# SkyKontrol-smartDisplay.net
KiCad netlist of a schematic drawn in EAGLE
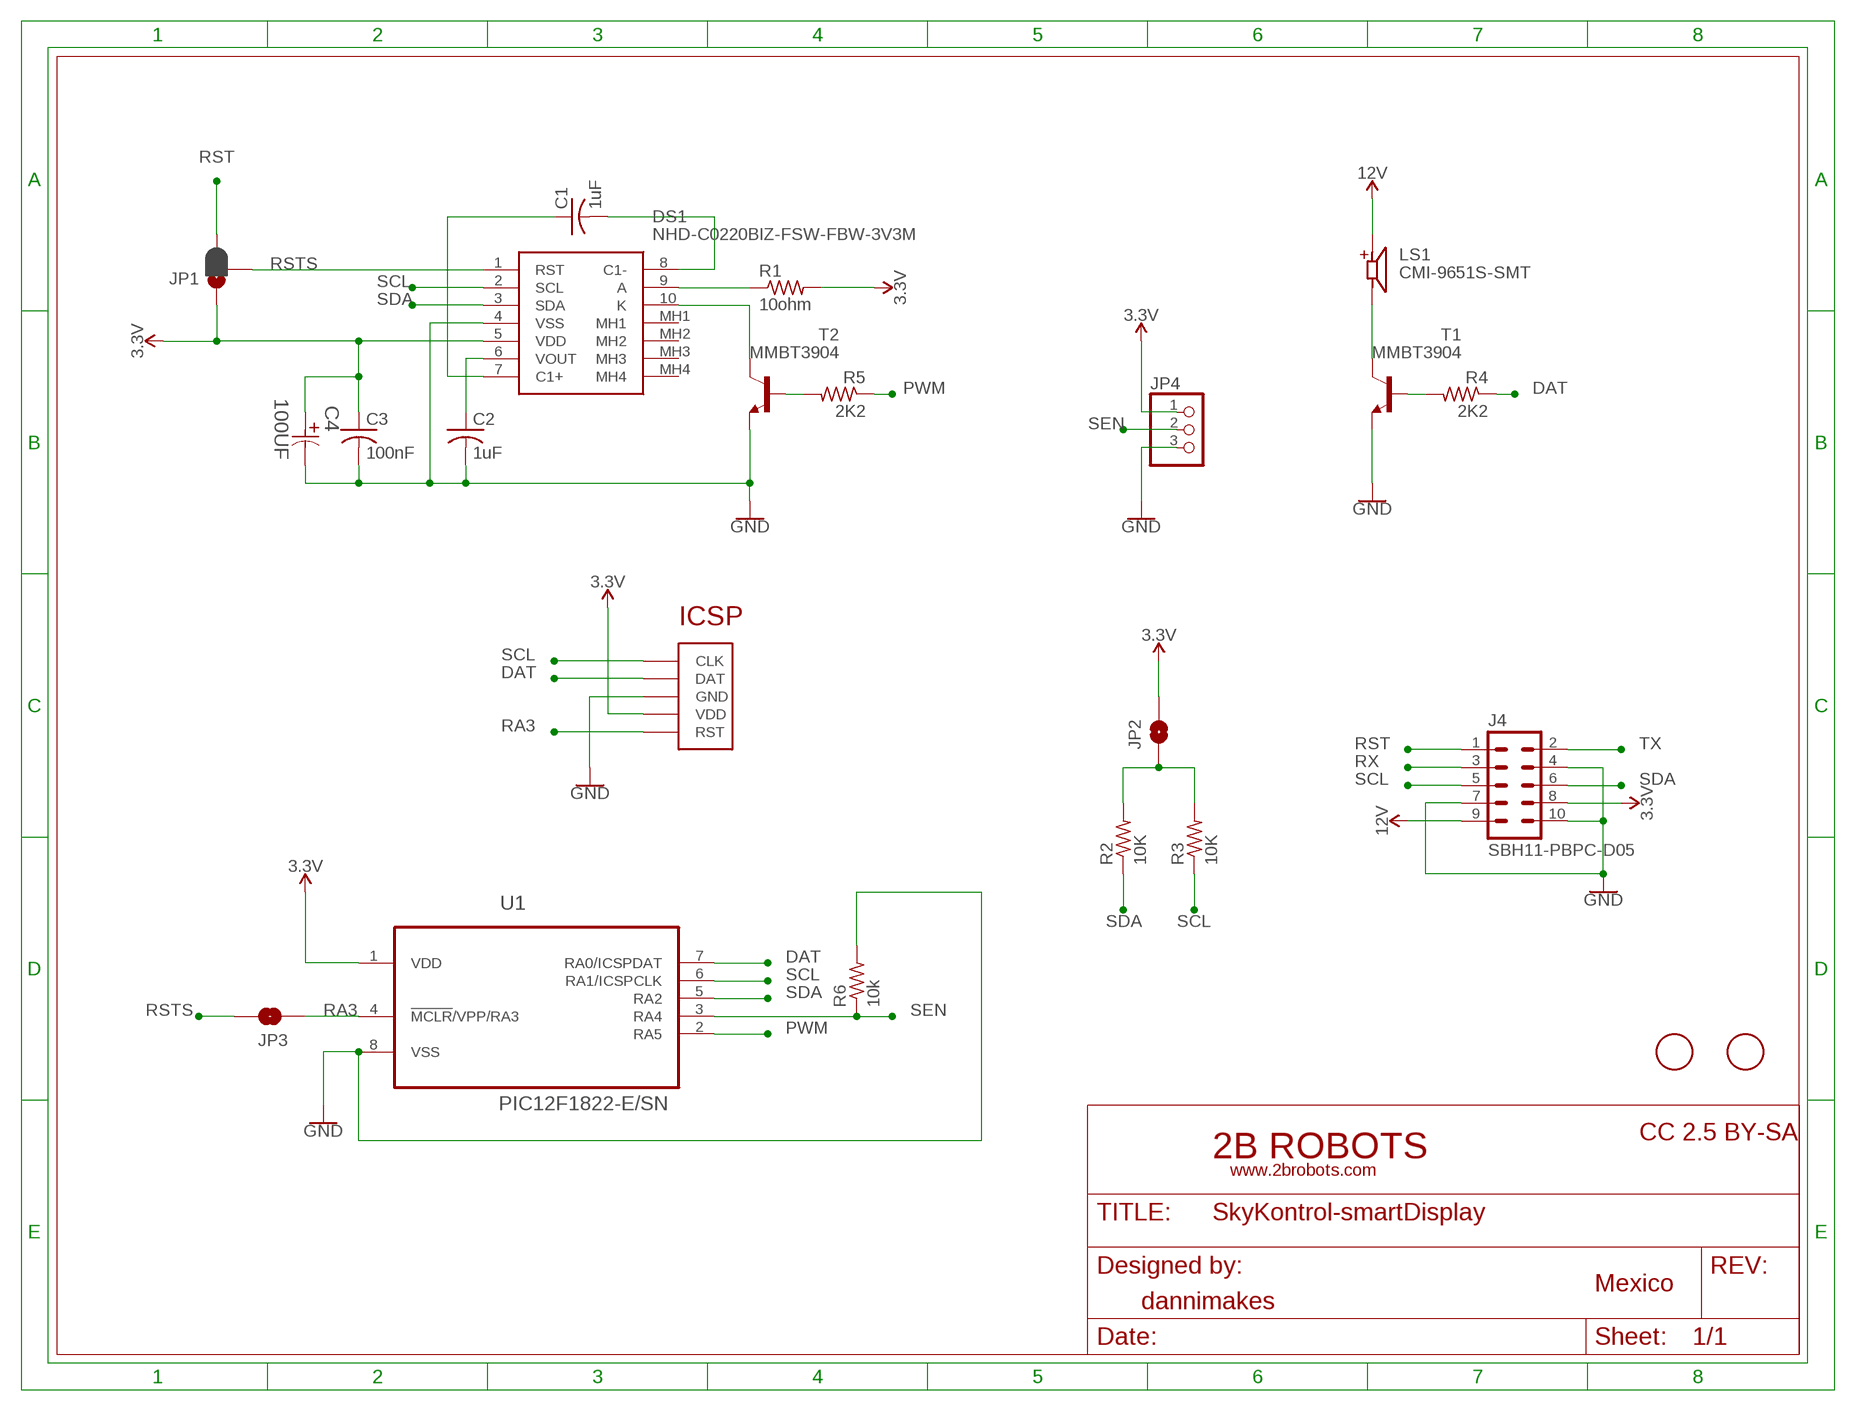
[diagram p0: schematic, sheet 1]

(export (version "E")
  (design (tool "Eeschema 10.0.6"))
  (components
    (comp (ref "C1")
      (value "1uF")
      (footprint "eagle-import:C0603K")
      (libsource (lib "eagle-import") (part "C-USC0603K"))
    )
    (comp (ref "C2")
      (value "1uF")
      (footprint "eagle-import:C0603K")
      (libsource (lib "eagle-import") (part "C-USC0603K"))
    )
    (comp (ref "C3")
      (value "100nF")
      (footprint "eagle-import:C0603K")
      (libsource (lib "eagle-import") (part "C-USC0603K"))
    )
    (comp (ref "C4")
      (value "100UF")
      (footprint "eagle-import:CAPAE660X800N")
      (fields (field (name "MPN") "EEE-HA1E101XP") (field (name "TOLERANCE") "±20 %"))
      (libsource (lib "eagle-import") (part "EEE--CASE-D8HA1E101XP"))
    )
    (comp (ref "DS1")
      (value "NHD-C0220BIZ-FSW-FBW-3V3M")
      (footprint "eagle-import:NHDC0220BIZFSWFBW3V3M")
      (fields (field (name "MOUSER_PART_NUMBER") "763-C0220BIZ-FSW-FBW"))
      (libsource (lib "eagle-import") (part "NHD-C0220BIZ-FSW-FBW-3V3M"))
    )
    (comp (ref "J4")
      (value "SBH11-PBPC-D05")
      (footprint "eagle-import:SBH11-PBPC-D05")
      (libsource (lib "eagle-import") (part "SBH11-PBPC-D05"))
    )
    (comp (ref "JP1")
      (value "JUMPER-SMT_3_1-NC_PASTE_SILK")
      (footprint "eagle-import:SMT-JUMPER_3_1-NC_PASTE_SILK")
      (libsource (lib "eagle-import") (part "JUMPER-SMT_3_1-NC_PASTE_SILK"))
    )
    (comp (ref "JP2")
      (value "JUMPER-SMT_2_NO_SILK")
      (footprint "eagle-import:SMT-JUMPER_2_NO_SILK")
      (libsource (lib "eagle-import") (part "JUMPER-SMT_2_NO_SILK"))
    )
    (comp (ref "JP3")
      (value "JUMPER-SMT_2_NO_SILK")
      (footprint "eagle-import:SMT-JUMPER_2_NO_SILK")
      (libsource (lib "eagle-import") (part "JUMPER-SMT_2_NO_SILK"))
    )
    (comp (ref "JP4")
      (value "PINHD-1X3CB")
      (footprint "eagle-import:1X03-CLEANBIG")
      (libsource (lib "eagle-import") (part "PINHD-1X3CB"))
    )
    (comp (ref "LS1")
      (value "CMI-9651S-SMT")
      (footprint "eagle-import:CUI_CMI-9651S-SMT")
      (fields (field (name "MANUFACTURER") "CUI INC"))
      (libsource (lib "eagle-import") (part "CMI-9651S-SMT"))
    )
    (comp (ref "R1")
      (value "10ohm")
      (footprint "eagle-import:R0805")
      (libsource (lib "eagle-import") (part "R-US_R0805"))
    )
    (comp (ref "R2")
      (value "10K")
      (footprint "eagle-import:R0805")
      (libsource (lib "eagle-import") (part "R-US_R0805"))
    )
    (comp (ref "R3")
      (value "10K")
      (footprint "eagle-import:R0805")
      (libsource (lib "eagle-import") (part "R-US_R0805"))
    )
    (comp (ref "R4")
      (value "2K2")
      (footprint "eagle-import:R0805")
      (libsource (lib "eagle-import") (part "R-US_R0805"))
    )
    (comp (ref "R5")
      (value "2K2")
      (footprint "eagle-import:R0805")
      (libsource (lib "eagle-import") (part "R-US_R0805"))
    )
    (comp (ref "R6")
      (value "10k")
      (footprint "eagle-import:R0805")
      (libsource (lib "eagle-import") (part "R-US_R0805"))
    )
    (comp (ref "T1")
      (value "MMBT3904")
      (footprint "eagle-import:SOT23-BEC")
      (libsource (lib "eagle-import") (part "-NPN-SOT23-BECMMBT3904LT1"))
    )
    (comp (ref "T2")
      (value "MMBT3904")
      (footprint "eagle-import:SOT23-BEC")
      (libsource (lib "eagle-import") (part "-NPN-SOT23-BECMMBT3904LT1"))
    )
    (comp (ref "U$1")
      (value "FIDUCIAL")
      (footprint "eagle-import:FIDUCIAL_1MM")
      (libsource (lib "eagle-import") (part "FIDUCIAL"))
    )
    (comp (ref "U$2")
      (value "ICSP_POGO")
      (footprint "eagle-import:ICSP_POGO")
      (libsource (lib "eagle-import") (part "ICSP_POGO"))
    )
    (comp (ref "U$3")
      (value "FIDUCIAL")
      (footprint "eagle-import:FIDUCIAL_1MM")
      (libsource (lib "eagle-import") (part "FIDUCIAL"))
    )
    (comp (ref "U1")
      (value "PIC12F1822-E/SN")
      (footprint "eagle-import:SOIC127P600X175-8N")
      (libsource (lib "eagle-import") (part "PIC12F1822-E/SN"))
    )
  )
  (nets
    (net (code "1") (name "/DAT") (class "Default")
      (node (ref "R4") (pin "1") (pinfunction "1_1") (pintype "passive"))
      (node (ref "U$2") (pin "P$4") (pinfunction "DAT_P$4") (pintype "bidirectional"))
      (node (ref "U1") (pin "7") (pinfunction "RA0/ICSPDAT_7") (pintype "bidirectional"))
    )
    (net (code "2") (name "/PWM") (class "Default")
      (node (ref "R5") (pin "1") (pinfunction "1_1") (pintype "passive"))
      (node (ref "U1") (pin "2") (pinfunction "RA5_2") (pintype "bidirectional"))
    )
    (net (code "3") (name "/RA3") (class "Default")
      (node (ref "JP3") (pin "1") (pinfunction "1_1") (pintype "passive"))
      (node (ref "U$2") (pin "P$1") (pinfunction "RST_P$1") (pintype "bidirectional"))
      (node (ref "U1") (pin "4") (pinfunction "~{MCLR}/VPP/RA3_4") (pintype "input"))
    )
    (net (code "4") (name "/RST") (class "Default")
      (node (ref "J4") (pin "1") (pinfunction "1_1") (pintype "passive"))
      (node (ref "JP1") (pin "3") (pinfunction "3_3") (pintype "passive"))
    )
    (net (code "5") (name "/RSTS") (class "Default")
      (node (ref "DS1") (pin "1") (pinfunction "RST_1") (pintype "bidirectional"))
      (node (ref "JP1") (pin "2") (pinfunction "2_2") (pintype "passive"))
      (node (ref "JP3") (pin "2") (pinfunction "2_2") (pintype "passive"))
    )
    (net (code "6") (name "/RX") (class "Default")
      (node (ref "J4") (pin "3") (pinfunction "3_3") (pintype "passive"))
    )
    (net (code "7") (name "/SCL") (class "Default")
      (node (ref "DS1") (pin "2") (pinfunction "SCL_2") (pintype "bidirectional"))
      (node (ref "J4") (pin "5") (pinfunction "5_5") (pintype "passive"))
      (node (ref "R3") (pin "1") (pinfunction "1_1") (pintype "passive"))
      (node (ref "U$2") (pin "P$5") (pinfunction "CLK_P$5") (pintype "bidirectional"))
      (node (ref "U1") (pin "6") (pinfunction "RA1/ICSPCLK_6") (pintype "bidirectional"))
    )
    (net (code "8") (name "/SDA") (class "Default")
      (node (ref "DS1") (pin "3") (pinfunction "SDA_3") (pintype "bidirectional"))
      (node (ref "J4") (pin "6") (pinfunction "6_6") (pintype "passive"))
      (node (ref "R2") (pin "1") (pinfunction "1_1") (pintype "passive"))
      (node (ref "U1") (pin "5") (pinfunction "RA2_5") (pintype "bidirectional"))
    )
    (net (code "9") (name "/SEN") (class "Default")
      (node (ref "JP4") (pin "2") (pinfunction "2_2") (pintype "passive"))
      (node (ref "R6") (pin "1") (pinfunction "1_1") (pintype "passive"))
      (node (ref "U1") (pin "3") (pinfunction "RA4_3") (pintype "bidirectional"))
    )
    (net (code "10") (name "/TX") (class "Default")
      (node (ref "J4") (pin "2") (pinfunction "2_2") (pintype "passive"))
    )
    (net (code "11") (name "3.3V") (class "Default")
      (node (ref "C3") (pin "1") (pinfunction "1_1") (pintype "passive"))
      (node (ref "C4") (pin "1") (pinfunction "1_1") (pintype "passive"))
      (node (ref "DS1") (pin "5") (pinfunction "VDD_5") (pintype "bidirectional"))
      (node (ref "J4") (pin "8") (pinfunction "8_8") (pintype "passive"))
      (node (ref "JP1") (pin "1") (pinfunction "1_1") (pintype "passive"))
      (node (ref "JP2") (pin "2") (pinfunction "2_2") (pintype "passive"))
      (node (ref "JP4") (pin "1") (pinfunction "1_1") (pintype "passive"))
      (node (ref "R1") (pin "2") (pinfunction "2_2") (pintype "passive"))
      (node (ref "U$2") (pin "P$2") (pinfunction "VDD_P$2") (pintype "bidirectional"))
      (node (ref "U1") (pin "1") (pinfunction "VDD_1") (pintype "power_in"))
    )
    (net (code "12") (name "12V") (class "Default")
      (node (ref "J4") (pin "9") (pinfunction "9_9") (pintype "passive"))
      (node (ref "LS1") (pin "P") (pinfunction "P_P") (pintype "passive"))
    )
    (net (code "13") (name "GND") (class "Default")
      (node (ref "C2") (pin "2") (pinfunction "2_2") (pintype "passive"))
      (node (ref "C3") (pin "2") (pinfunction "2_2") (pintype "passive"))
      (node (ref "C4") (pin "2") (pinfunction "2_2") (pintype "passive"))
      (node (ref "DS1") (pin "4") (pinfunction "VSS_4") (pintype "bidirectional"))
      (node (ref "J4") (pin "10") (pinfunction "10_10") (pintype "passive"))
      (node (ref "J4") (pin "4") (pinfunction "4_4") (pintype "passive"))
      (node (ref "J4") (pin "7") (pinfunction "7_7") (pintype "passive"))
      (node (ref "JP4") (pin "3") (pinfunction "3_3") (pintype "passive"))
      (node (ref "R6") (pin "2") (pinfunction "2_2") (pintype "passive"))
      (node (ref "T1") (pin "E") (pinfunction "E_E") (pintype "passive"))
      (node (ref "T2") (pin "E") (pinfunction "E_E") (pintype "passive"))
      (node (ref "U$2") (pin "P$3") (pinfunction "GND_P$3") (pintype "bidirectional"))
      (node (ref "U1") (pin "8") (pinfunction "VSS_8") (pintype "power_in"))
    )
    (net (code "14") (name "Net-(DS1-A)") (class "Default")
      (node (ref "DS1") (pin "9") (pinfunction "A_9") (pintype "bidirectional"))
      (node (ref "R1") (pin "1") (pinfunction "1_1") (pintype "passive"))
    )
    (net (code "15") (name "Net-(DS1-C1+)") (class "Default")
      (node (ref "C1") (pin "1") (pinfunction "1_1") (pintype "passive"))
      (node (ref "DS1") (pin "7") (pinfunction "C1+_7") (pintype "bidirectional"))
    )
    (net (code "16") (name "Net-(DS1-C1-)") (class "Default")
      (node (ref "C1") (pin "2") (pinfunction "2_2") (pintype "passive"))
      (node (ref "DS1") (pin "8") (pinfunction "C1-_8") (pintype "bidirectional"))
    )
    (net (code "17") (name "Net-(DS1-K)") (class "Default")
      (node (ref "DS1") (pin "10") (pinfunction "K_10") (pintype "bidirectional"))
      (node (ref "T2") (pin "C") (pinfunction "C_C") (pintype "passive"))
    )
    (net (code "18") (name "Net-(DS1-VOUT)") (class "Default")
      (node (ref "C2") (pin "1") (pinfunction "1_1") (pintype "passive"))
      (node (ref "DS1") (pin "6") (pinfunction "VOUT_6") (pintype "bidirectional"))
    )
    (net (code "19") (name "Net-(JP2-Pad1)") (class "Default")
      (node (ref "JP2") (pin "1") (pinfunction "1_1") (pintype "passive"))
      (node (ref "R2") (pin "2") (pinfunction "2_2") (pintype "passive"))
      (node (ref "R3") (pin "2") (pinfunction "2_2") (pintype "passive"))
    )
    (net (code "20") (name "Net-(LS1-PadN)") (class "Default")
      (node (ref "LS1") (pin "N") (pinfunction "N_N") (pintype "passive"))
      (node (ref "T1") (pin "C") (pinfunction "C_C") (pintype "passive"))
    )
    (net (code "21") (name "Net-(R4-Pad2)") (class "Default")
      (node (ref "R4") (pin "2") (pinfunction "2_2") (pintype "passive"))
      (node (ref "T1") (pin "B") (pinfunction "B_B") (pintype "passive"))
    )
    (net (code "22") (name "Net-(R5-Pad2)") (class "Default")
      (node (ref "R5") (pin "2") (pinfunction "2_2") (pintype "passive"))
      (node (ref "T2") (pin "B") (pinfunction "B_B") (pintype "passive"))
    )
    (net (code "23") (name "unconnected-(DS1-PadMH1)") (class "Default")
      (node (ref "DS1") (pin "MH1") (pinfunction "MH1_MH1") (pintype "bidirectional"))
    )
    (net (code "24") (name "unconnected-(DS1-PadMH2)") (class "Default")
      (node (ref "DS1") (pin "MH2") (pinfunction "MH2_MH2") (pintype "bidirectional"))
    )
    (net (code "25") (name "unconnected-(DS1-PadMH3)") (class "Default")
      (node (ref "DS1") (pin "MH3") (pinfunction "MH3_MH3") (pintype "bidirectional"))
    )
    (net (code "26") (name "unconnected-(DS1-PadMH4)") (class "Default")
      (node (ref "DS1") (pin "MH4") (pinfunction "MH4_MH4") (pintype "bidirectional"))
    )
  )
)
